# GPS.net
KiCad netlist of a schematic drawn in Altium Designer
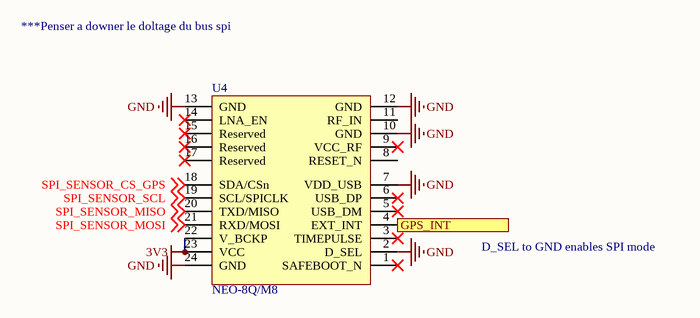
[diagram p0: GPS.SchDoc]

(export (version "E")
  (design (tool "Eeschema 10.0.6"))
  (components
    (comp (ref "U4")
      (value "NEO-8Q/M8")
      (footprint "NEO-8Q/M8")
      (libsource (lib "U96_SchLib") (part "NEO-8Q/M8"))
    )
  )
  (nets
    (net (code "1") (name "/GPS_INT") (class "Default")
      (node (ref "U4") (pin "4") (pinfunction "EXT_INT_4") (pintype "passive"))
    )
    (net (code "2") (name "3V3") (class "Default")
      (node (ref "U4") (pin "22") (pinfunction "V_BCKP_22") (pintype "passive"))
      (node (ref "U4") (pin "23") (pinfunction "VCC_23") (pintype "passive"))
    )
    (net (code "3") (name "GND") (class "Default")
      (node (ref "U4") (pin "10") (pinfunction "GND_10") (pintype "passive"))
      (node (ref "U4") (pin "12") (pinfunction "GND_12") (pintype "passive"))
      (node (ref "U4") (pin "13") (pinfunction "GND_13") (pintype "passive"))
      (node (ref "U4") (pin "2") (pinfunction "D_SEL_2") (pintype "passive"))
      (node (ref "U4") (pin "24") (pinfunction "GND_24") (pintype "passive"))
      (node (ref "U4") (pin "7") (pinfunction "VDD_USB_7") (pintype "passive"))
    )
    (net (code "4") (name "SPI_SENSOR_CS_GPS") (class "Default")
      (node (ref "U4") (pin "18") (pinfunction "SDA/CSn_18") (pintype "passive"))
    )
    (net (code "5") (name "SPI_SENSOR_MISO") (class "Default")
      (node (ref "U4") (pin "20") (pinfunction "TXD/MISO_20") (pintype "passive"))
    )
    (net (code "6") (name "SPI_SENSOR_MOSI") (class "Default")
      (node (ref "U4") (pin "21") (pinfunction "RXD/MOSI_21") (pintype "passive"))
    )
    (net (code "7") (name "SPI_SENSOR_SCL") (class "Default")
      (node (ref "U4") (pin "19") (pinfunction "SCL/SPICLK_19") (pintype "passive"))
    )
    (net (code "8") (name "unconnected-(U4-LNA_EN-Pad14)") (class "Default")
      (node (ref "U4") (pin "14") (pinfunction "LNA_EN_14") (pintype "passive+no_connect"))
    )
    (net (code "9") (name "unconnected-(U4-RESET_N-Pad8)") (class "Default")
      (node (ref "U4") (pin "8") (pinfunction "RESET_N_8") (pintype "passive"))
    )
    (net (code "10") (name "unconnected-(U4-RF_IN-Pad11)") (class "Default")
      (node (ref "U4") (pin "11") (pinfunction "RF_IN_11") (pintype "passive"))
    )
    (net (code "11") (name "unconnected-(U4-Reserved-Pad15)") (class "Default")
      (node (ref "U4") (pin "15") (pinfunction "Reserved_15") (pintype "passive+no_connect"))
    )
    (net (code "12") (name "unconnected-(U4-Reserved-Pad16)") (class "Default")
      (node (ref "U4") (pin "16") (pinfunction "Reserved_16") (pintype "passive+no_connect"))
    )
    (net (code "13") (name "unconnected-(U4-Reserved-Pad17)") (class "Default")
      (node (ref "U4") (pin "17") (pinfunction "Reserved_17") (pintype "passive+no_connect"))
    )
    (net (code "14") (name "unconnected-(U4-SAFEBOOT_N-Pad1)") (class "Default")
      (node (ref "U4") (pin "1") (pinfunction "SAFEBOOT_N_1") (pintype "passive+no_connect"))
    )
    (net (code "15") (name "unconnected-(U4-TIMEPULSE-Pad3)") (class "Default")
      (node (ref "U4") (pin "3") (pinfunction "TIMEPULSE_3") (pintype "passive+no_connect"))
    )
    (net (code "16") (name "unconnected-(U4-USB_DM-Pad5)") (class "Default")
      (node (ref "U4") (pin "5") (pinfunction "USB_DM_5") (pintype "passive+no_connect"))
    )
    (net (code "17") (name "unconnected-(U4-USB_DP-Pad6)") (class "Default")
      (node (ref "U4") (pin "6") (pinfunction "USB_DP_6") (pintype "passive+no_connect"))
    )
    (net (code "18") (name "unconnected-(U4-VCC_RF-Pad9)") (class "Default")
      (node (ref "U4") (pin "9") (pinfunction "VCC_RF_9") (pintype "passive+no_connect"))
    )
  )
)
